# Schematic.net
KiCad netlist of a schematic drawn in Altium Designer
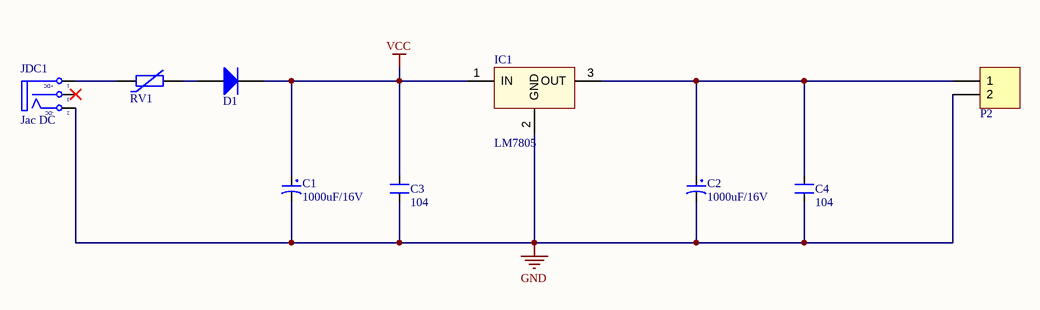
[diagram p0: Schematic.SchDoc]

(export (version "E")
  (design (tool "Eeschema 10.0.6"))
  (components
    (comp (ref "C1")
      (value "1000uF/16V")
      (footprint "CP1.5/3.4")
      (description "Cap 1000uF/16V - 220uF/50V")
      (libsource (lib "KhanhBK_SCH_Library_2") (part "CP4"))
    )
    (comp (ref "C2")
      (value "1000uF/16V")
      (footprint "CP1.5/3.4")
      (description "Cap 1000uF/16V - 220uF/50V")
      (libsource (lib "KhanhBK_SCH_Library_2") (part "CP4"))
    )
    (comp (ref "C3")
      (value "104")
      (footprint "CN2")
      (description "Cap np 104 => 105pF")
      (libsource (lib "KhanhBK_SCH_Library_2") (part "CN2"))
    )
    (comp (ref "C4")
      (value "104")
      (footprint "CN2")
      (description "Cap np 104 => 105pF")
      (libsource (lib "KhanhBK_SCH_Library_2") (part "CN2"))
    )
    (comp (ref "D1")
      (value "Diode")
      (footprint "D1A")
      (description "Default Diode")
      (libsource (lib "PIF_Library") (part "Diode"))
    )
    (comp (ref "IC1")
      (value "LM7805")
      (footprint "QTO-220")
      (description "On ap +, from + 5 to + 24VDC")
      (libsource (lib "KhanhBK_SCH_Library_2") (part "LM78xx"))
    )
    (comp (ref "JDC1")
      (value "Jac DC")
      (footprint "DC-IN")
      (description "Jac DC input")
      (libsource (lib "KhanhBK_SCH_Library_2") (part "DCIN"))
    )
    (comp (ref "P2")
      (value "Domino 2")
      (footprint "DOMINO 2- 5mm")
      (description "Domino, 2-Pin")
      (fields (field (name "PUBLISHER") "Altium Limited"))
      (libsource (lib "PIF_Library") (part "Domino 2"))
    )
    (comp (ref "RV1")
      (value "14VAC, 18VDC")
      (footprint "D9W4.5H12P0.8")
      (description "WE-VD Disk Varistor, THT, 14VAC, 18VDC, 2930pF")
      (fields
        (field (name "MANUFACTURER PART NUMBER") "820571406")
        (field (name "MANUFACTURER") "Wurth Elektronik")
      )
      (libsource (lib "Altium_WE-VD (rev23a)") (part "820571406"))
    )
  )
  (nets
    (net (code "1") (name "GND") (class "Default")
      (node (ref "C1") (pin "2") (pinfunction "2_2") (pintype "passive"))
      (node (ref "C2") (pin "2") (pinfunction "2_2") (pintype "passive"))
      (node (ref "C3") (pin "1") (pinfunction "1_1") (pintype "passive"))
      (node (ref "C4") (pin "1") (pinfunction "1_1") (pintype "passive"))
      (node (ref "IC1") (pin "2") (pinfunction "GND_2") (pintype "passive"))
      (node (ref "JDC1") (pin "2") (pinfunction "TN_2") (pintype "passive"))
      (node (ref "P2") (pin "2") (pinfunction "2_2") (pintype "passive"))
    )
    (net (code "2") (name "Net-(D1-A)") (class "Default")
      (node (ref "D1") (pin "1") (pinfunction "A_1") (pintype "passive"))
      (node (ref "RV1") (pin "2") (pinfunction "2_2") (pintype "passive"))
    )
    (net (code "3") (name "Net-(IC1-OUT)") (class "Default")
      (node (ref "C2") (pin "1") (pinfunction "1_1") (pintype "passive"))
      (node (ref "C4") (pin "2") (pinfunction "2_2") (pintype "passive"))
      (node (ref "IC1") (pin "3") (pinfunction "OUT_3") (pintype "passive"))
      (node (ref "P2") (pin "1") (pinfunction "1_1") (pintype "passive"))
    )
    (net (code "4") (name "Net-(JDC1-T)") (class "Default")
      (node (ref "JDC1") (pin "1") (pinfunction "T_1") (pintype "passive"))
      (node (ref "RV1") (pin "1") (pinfunction "1_1") (pintype "passive"))
    )
    (net (code "5") (name "VCC") (class "Default")
      (node (ref "C1") (pin "1") (pinfunction "1_1") (pintype "passive"))
      (node (ref "C3") (pin "2") (pinfunction "2_2") (pintype "passive"))
      (node (ref "D1") (pin "2") (pinfunction "K_2") (pintype "passive"))
      (node (ref "IC1") (pin "1") (pinfunction "IN_1") (pintype "passive"))
    )
    (net (code "6") (name "unconnected-(JDC1-S-Pad3)") (class "Default")
      (node (ref "JDC1") (pin "3") (pinfunction "S_3") (pintype "power_in+no_connect"))
    )
  )
)
